# controller_left_bottom.net
KiCad netlist of a schematic drawn in EAGLE
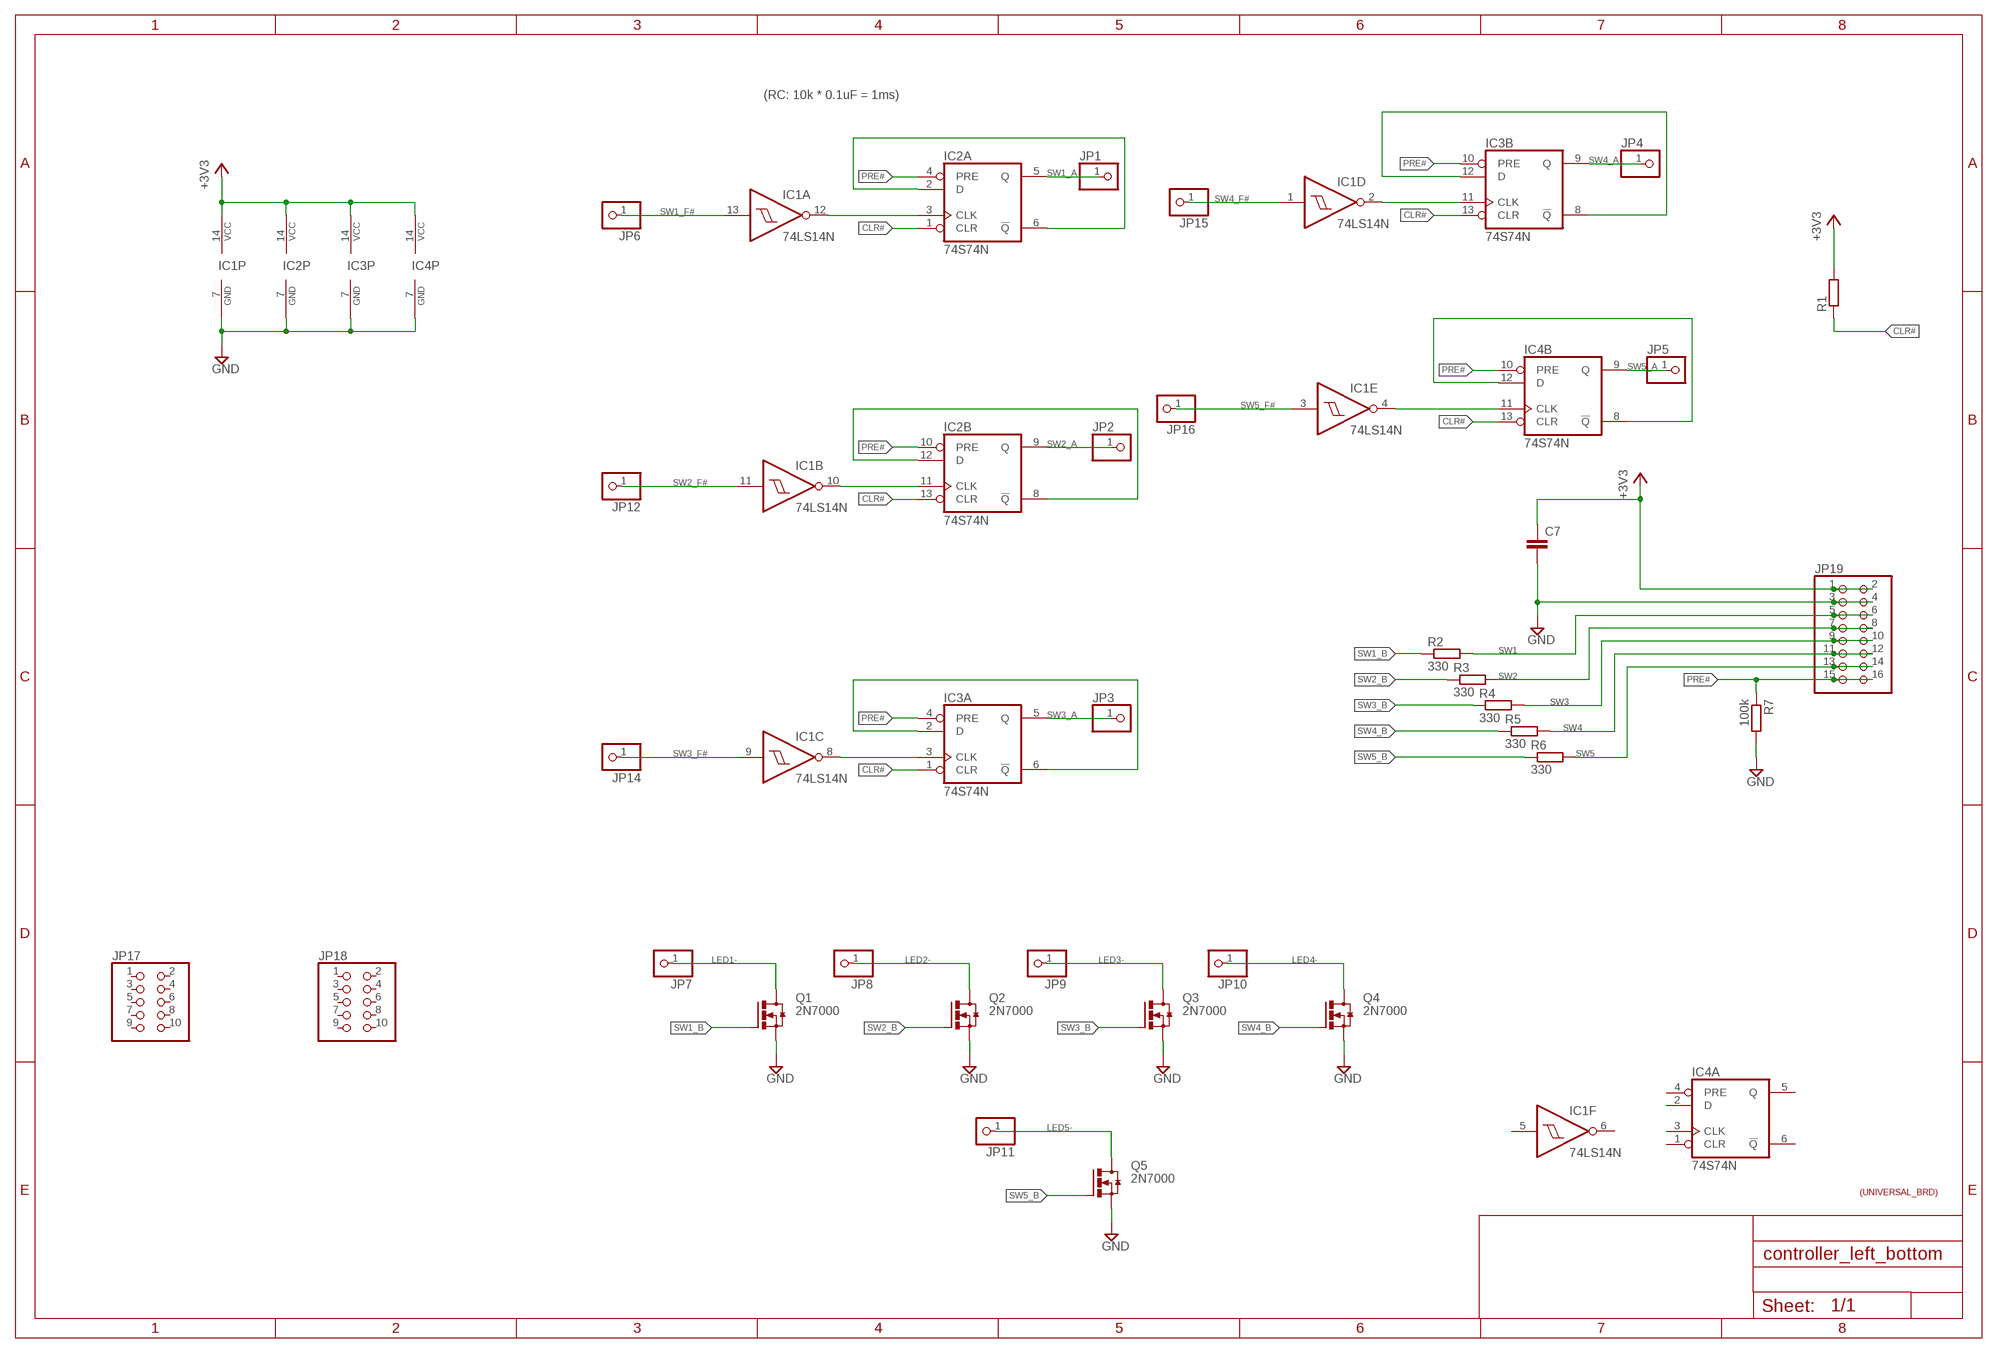
[diagram p0: schematic, sheet 1]

(export (version "E")
  (design (tool "Eeschema 10.0.6"))
  (components
    (comp (ref "C7")
      (value "C_DIP_2.54_1")
      (footprint "eagle-import:C_DIP2.54_1")
      (libsource (lib "eagle-import") (part "C_DIP_2.54_1"))
    )
    (comp (ref "IC1")
      (value "74LS14N")
      (footprint "eagle-import:DIL14")
      (libsource (lib "eagle-import") (part "7414NLS"))
    )
    (comp (ref "IC2")
      (value "74S74N")
      (footprint "eagle-import:DIL14")
      (libsource (lib "eagle-import") (part "7474NS"))
    )
    (comp (ref "IC3")
      (value "74S74N")
      (footprint "eagle-import:DIL14")
      (libsource (lib "eagle-import") (part "7474NS"))
    )
    (comp (ref "IC4")
      (value "74S74N")
      (footprint "eagle-import:DIL14")
      (libsource (lib "eagle-import") (part "7474NS"))
    )
    (comp (ref "JP1")
      (value "PINHD-1X1")
      (footprint "eagle-import:1X01_UNIVERSAL_BRD")
      (libsource (lib "eagle-import") (part "PINHD-1X1"))
    )
    (comp (ref "JP2")
      (value "PINHD-1X1")
      (footprint "eagle-import:1X01_UNIVERSAL_BRD")
      (libsource (lib "eagle-import") (part "PINHD-1X1"))
    )
    (comp (ref "JP3")
      (value "PINHD-1X1")
      (footprint "eagle-import:1X01_UNIVERSAL_BRD")
      (libsource (lib "eagle-import") (part "PINHD-1X1"))
    )
    (comp (ref "JP4")
      (value "PINHD-1X1")
      (footprint "eagle-import:1X01_UNIVERSAL_BRD")
      (libsource (lib "eagle-import") (part "PINHD-1X1"))
    )
    (comp (ref "JP5")
      (value "PINHD-1X1")
      (footprint "eagle-import:1X01_UNIVERSAL_BRD")
      (libsource (lib "eagle-import") (part "PINHD-1X1"))
    )
    (comp (ref "JP6")
      (value "PINHD-1X1")
      (footprint "eagle-import:1X01_UNIVERSAL_BRD")
      (libsource (lib "eagle-import") (part "PINHD-1X1"))
    )
    (comp (ref "JP7")
      (value "PINHD-1X1")
      (footprint "eagle-import:1X01_UNIVERSAL_BRD")
      (libsource (lib "eagle-import") (part "PINHD-1X1"))
    )
    (comp (ref "JP8")
      (value "PINHD-1X1")
      (footprint "eagle-import:1X01_UNIVERSAL_BRD")
      (libsource (lib "eagle-import") (part "PINHD-1X1"))
    )
    (comp (ref "JP9")
      (value "PINHD-1X1")
      (footprint "eagle-import:1X01_UNIVERSAL_BRD")
      (libsource (lib "eagle-import") (part "PINHD-1X1"))
    )
    (comp (ref "JP10")
      (value "PINHD-1X1")
      (footprint "eagle-import:1X01_UNIVERSAL_BRD")
      (libsource (lib "eagle-import") (part "PINHD-1X1"))
    )
    (comp (ref "JP11")
      (value "PINHD-1X1")
      (footprint "eagle-import:1X01_UNIVERSAL_BRD")
      (libsource (lib "eagle-import") (part "PINHD-1X1"))
    )
    (comp (ref "JP12")
      (value "PINHD-1X1")
      (footprint "eagle-import:1X01_UNIVERSAL_BRD")
      (libsource (lib "eagle-import") (part "PINHD-1X1"))
    )
    (comp (ref "JP14")
      (value "PINHD-1X1")
      (footprint "eagle-import:1X01_UNIVERSAL_BRD")
      (libsource (lib "eagle-import") (part "PINHD-1X1"))
    )
    (comp (ref "JP15")
      (value "PINHD-1X1")
      (footprint "eagle-import:1X01_UNIVERSAL_BRD")
      (libsource (lib "eagle-import") (part "PINHD-1X1"))
    )
    (comp (ref "JP16")
      (value "PINHD-1X1")
      (footprint "eagle-import:1X01_UNIVERSAL_BRD")
      (libsource (lib "eagle-import") (part "PINHD-1X1"))
    )
    (comp (ref "JP17")
      (value "PINHD-2X5")
      (footprint "eagle-import:2X05")
      (libsource (lib "eagle-import") (part "PINHD-2X5"))
    )
    (comp (ref "JP18")
      (value "PINHD-2X5")
      (footprint "eagle-import:2X05")
      (libsource (lib "eagle-import") (part "PINHD-2X5"))
    )
    (comp (ref "JP19")
      (value "PINHD-2X8")
      (footprint "eagle-import:2X08")
      (libsource (lib "eagle-import") (part "PINHD-2X8"))
    )
    (comp (ref "Q1")
      (value "2N7000")
      (footprint "eagle-import:TO92")
      (libsource (lib "eagle-import") (part "2N7000"))
    )
    (comp (ref "Q2")
      (value "2N7000")
      (footprint "eagle-import:TO92")
      (libsource (lib "eagle-import") (part "2N7000"))
    )
    (comp (ref "Q3")
      (value "2N7000")
      (footprint "eagle-import:TO92")
      (libsource (lib "eagle-import") (part "2N7000"))
    )
    (comp (ref "Q4")
      (value "2N7000")
      (footprint "eagle-import:TO92")
      (libsource (lib "eagle-import") (part "2N7000"))
    )
    (comp (ref "Q5")
      (value "2N7000")
      (footprint "eagle-import:TO92")
      (libsource (lib "eagle-import") (part "2N7000"))
    )
    (comp (ref "R1")
      (value "R_DIP_4")
      (footprint "eagle-import:R_DIP2.54_4")
      (libsource (lib "eagle-import") (part "R_DIP_4"))
    )
    (comp (ref "R2")
      (value "330")
      (footprint "eagle-import:R_DIP2.54_4")
      (libsource (lib "eagle-import") (part "R_DIP_4"))
    )
    (comp (ref "R3")
      (value "330")
      (footprint "eagle-import:R_DIP2.54_4")
      (libsource (lib "eagle-import") (part "R_DIP_4"))
    )
    (comp (ref "R4")
      (value "330")
      (footprint "eagle-import:R_DIP2.54_4")
      (libsource (lib "eagle-import") (part "R_DIP_4"))
    )
    (comp (ref "R5")
      (value "330")
      (footprint "eagle-import:R_DIP2.54_4")
      (libsource (lib "eagle-import") (part "R_DIP_4"))
    )
    (comp (ref "R6")
      (value "330")
      (footprint "eagle-import:R_DIP2.54_4")
      (libsource (lib "eagle-import") (part "R_DIP_4"))
    )
    (comp (ref "R7")
      (value "100k")
      (footprint "eagle-import:R_DIP2.54_4")
      (libsource (lib "eagle-import") (part "R_DIP_4"))
    )
    (comp (ref "U$1")
      (value "UNIVERSAL_BRD_95MM_72MM")
      (footprint "eagle-import:UNIVERSAL_BRD_95MM_72MM")
      (libsource (lib "eagle-import") (part "UNIVERSAL_BRD_95MM_72MM"))
    )
  )
  (nets
    (net (code "1") (name "+3V3") (class "Default")
      (node (ref "C7") (pin "1") (pinfunction "1_1") (pintype "passive"))
      (node (ref "IC1") (pin "14") (pinfunction "VCC_14") (pintype "power_in"))
      (node (ref "IC2") (pin "14") (pinfunction "VCC_14") (pintype "power_in"))
      (node (ref "IC3") (pin "14") (pinfunction "VCC_14") (pintype "power_in"))
      (node (ref "IC4") (pin "14") (pinfunction "VCC_14") (pintype "power_in"))
      (node (ref "JP19") (pin "1") (pinfunction "1_1") (pintype "passive"))
      (node (ref "JP19") (pin "2") (pinfunction "2_2") (pintype "passive"))
      (node (ref "R1") (pin "2") (pinfunction "2_2") (pintype "passive"))
    )
    (net (code "2") (name "/LED1-") (class "Default")
      (node (ref "JP7") (pin "1") (pinfunction "1_1") (pintype "passive"))
      (node (ref "Q1") (pin "D") (pinfunction "D_D") (pintype "passive"))
    )
    (net (code "3") (name "/LED2-") (class "Default")
      (node (ref "JP8") (pin "1") (pinfunction "1_1") (pintype "passive"))
      (node (ref "Q2") (pin "D") (pinfunction "D_D") (pintype "passive"))
    )
    (net (code "4") (name "/LED3-") (class "Default")
      (node (ref "JP9") (pin "1") (pinfunction "1_1") (pintype "passive"))
      (node (ref "Q3") (pin "D") (pinfunction "D_D") (pintype "passive"))
    )
    (net (code "5") (name "/LED4-") (class "Default")
      (node (ref "JP10") (pin "1") (pinfunction "1_1") (pintype "passive"))
      (node (ref "Q4") (pin "D") (pinfunction "D_D") (pintype "passive"))
    )
    (net (code "6") (name "/LED5-") (class "Default")
      (node (ref "JP11") (pin "1") (pinfunction "1_1") (pintype "passive"))
      (node (ref "Q5") (pin "D") (pinfunction "D_D") (pintype "passive"))
    )
    (net (code "7") (name "/SW1") (class "Default")
      (node (ref "JP19") (pin "5") (pinfunction "5_5") (pintype "passive"))
      (node (ref "JP19") (pin "6") (pinfunction "6_6") (pintype "passive"))
      (node (ref "R2") (pin "2") (pinfunction "2_2") (pintype "passive"))
    )
    (net (code "8") (name "/SW1_A") (class "Default")
      (node (ref "IC2") (pin "5") (pinfunction "Q_5") (pintype "output"))
      (node (ref "JP1") (pin "1") (pinfunction "1_1") (pintype "passive"))
    )
    (net (code "9") (name "/SW1_F#") (class "Default")
      (node (ref "IC1") (pin "13") (pinfunction "I_13") (pintype "input"))
      (node (ref "JP6") (pin "1") (pinfunction "1_1") (pintype "passive"))
    )
    (net (code "10") (name "/SW2") (class "Default")
      (node (ref "JP19") (pin "7") (pinfunction "7_7") (pintype "passive"))
      (node (ref "JP19") (pin "8") (pinfunction "8_8") (pintype "passive"))
      (node (ref "R3") (pin "2") (pinfunction "2_2") (pintype "passive"))
    )
    (net (code "11") (name "/SW2_A") (class "Default")
      (node (ref "IC2") (pin "9") (pinfunction "Q_9") (pintype "output"))
      (node (ref "JP2") (pin "1") (pinfunction "1_1") (pintype "passive"))
    )
    (net (code "12") (name "/SW2_F#") (class "Default")
      (node (ref "IC1") (pin "11") (pinfunction "I_11") (pintype "input"))
      (node (ref "JP12") (pin "1") (pinfunction "1_1") (pintype "passive"))
    )
    (net (code "13") (name "/SW3") (class "Default")
      (node (ref "JP19") (pin "10") (pinfunction "10_10") (pintype "passive"))
      (node (ref "JP19") (pin "9") (pinfunction "9_9") (pintype "passive"))
      (node (ref "R4") (pin "2") (pinfunction "2_2") (pintype "passive"))
    )
    (net (code "14") (name "/SW3_A") (class "Default")
      (node (ref "IC3") (pin "5") (pinfunction "Q_5") (pintype "output"))
      (node (ref "JP3") (pin "1") (pinfunction "1_1") (pintype "passive"))
    )
    (net (code "15") (name "/SW3_F#") (class "Default")
      (node (ref "IC1") (pin "9") (pinfunction "I_9") (pintype "input"))
      (node (ref "JP14") (pin "1") (pinfunction "1_1") (pintype "passive"))
    )
    (net (code "16") (name "/SW4") (class "Default")
      (node (ref "JP19") (pin "11") (pinfunction "11_11") (pintype "passive"))
      (node (ref "JP19") (pin "12") (pinfunction "12_12") (pintype "passive"))
      (node (ref "R5") (pin "2") (pinfunction "2_2") (pintype "passive"))
    )
    (net (code "17") (name "/SW4_A") (class "Default")
      (node (ref "IC3") (pin "9") (pinfunction "Q_9") (pintype "output"))
      (node (ref "JP4") (pin "1") (pinfunction "1_1") (pintype "passive"))
    )
    (net (code "18") (name "/SW4_F#") (class "Default")
      (node (ref "IC1") (pin "1") (pinfunction "I_1") (pintype "input"))
      (node (ref "JP15") (pin "1") (pinfunction "1_1") (pintype "passive"))
    )
    (net (code "19") (name "/SW5") (class "Default")
      (node (ref "JP19") (pin "13") (pinfunction "13_13") (pintype "passive"))
      (node (ref "JP19") (pin "14") (pinfunction "14_14") (pintype "passive"))
      (node (ref "R6") (pin "2") (pinfunction "2_2") (pintype "passive"))
    )
    (net (code "20") (name "/SW5_A") (class "Default")
      (node (ref "IC4") (pin "9") (pinfunction "Q_9") (pintype "output"))
      (node (ref "JP5") (pin "1") (pinfunction "1_1") (pintype "passive"))
    )
    (net (code "21") (name "/SW5_F#") (class "Default")
      (node (ref "IC1") (pin "3") (pinfunction "I_3") (pintype "input"))
      (node (ref "JP16") (pin "1") (pinfunction "1_1") (pintype "passive"))
    )
    (net (code "22") (name "CLR#") (class "Default")
      (node (ref "IC2") (pin "1") (pinfunction "CLR_1") (pintype "input"))
      (node (ref "IC2") (pin "13") (pinfunction "CLR_13") (pintype "input"))
      (node (ref "IC3") (pin "1") (pinfunction "CLR_1") (pintype "input"))
      (node (ref "IC3") (pin "13") (pinfunction "CLR_13") (pintype "input"))
      (node (ref "IC4") (pin "13") (pinfunction "CLR_13") (pintype "input"))
      (node (ref "R1") (pin "1") (pinfunction "1_1") (pintype "passive"))
    )
    (net (code "23") (name "GND") (class "Default")
      (node (ref "C7") (pin "2") (pinfunction "2_2") (pintype "passive"))
      (node (ref "IC1") (pin "7") (pinfunction "GND_7") (pintype "power_in"))
      (node (ref "IC2") (pin "7") (pinfunction "GND_7") (pintype "power_in"))
      (node (ref "IC3") (pin "7") (pinfunction "GND_7") (pintype "power_in"))
      (node (ref "IC4") (pin "7") (pinfunction "GND_7") (pintype "power_in"))
      (node (ref "JP19") (pin "3") (pinfunction "3_3") (pintype "passive"))
      (node (ref "JP19") (pin "4") (pinfunction "4_4") (pintype "passive"))
      (node (ref "Q1") (pin "S") (pinfunction "S_S") (pintype "passive"))
      (node (ref "Q2") (pin "S") (pinfunction "S_S") (pintype "passive"))
      (node (ref "Q3") (pin "S") (pinfunction "S_S") (pintype "passive"))
      (node (ref "Q4") (pin "S") (pinfunction "S_S") (pintype "passive"))
      (node (ref "Q5") (pin "S") (pinfunction "S_S") (pintype "passive"))
      (node (ref "R7") (pin "2") (pinfunction "2_2") (pintype "passive"))
    )
    (net (code "24") (name "Net-(IC1A-O)") (class "Default")
      (node (ref "IC1") (pin "12") (pinfunction "O_12") (pintype "output"))
      (node (ref "IC2") (pin "3") (pinfunction "CLK_3") (pintype "input"))
    )
    (net (code "25") (name "Net-(IC1B-O)") (class "Default")
      (node (ref "IC1") (pin "10") (pinfunction "O_10") (pintype "output"))
      (node (ref "IC2") (pin "11") (pinfunction "CLK_11") (pintype "input"))
    )
    (net (code "26") (name "Net-(IC1C-O)") (class "Default")
      (node (ref "IC1") (pin "8") (pinfunction "O_8") (pintype "output"))
      (node (ref "IC3") (pin "3") (pinfunction "CLK_3") (pintype "input"))
    )
    (net (code "27") (name "Net-(IC1D-O)") (class "Default")
      (node (ref "IC1") (pin "2") (pinfunction "O_2") (pintype "output"))
      (node (ref "IC3") (pin "11") (pinfunction "CLK_11") (pintype "input"))
    )
    (net (code "28") (name "Net-(IC1E-O)") (class "Default")
      (node (ref "IC1") (pin "4") (pinfunction "O_4") (pintype "output"))
      (node (ref "IC4") (pin "11") (pinfunction "CLK_11") (pintype "input"))
    )
    (net (code "29") (name "Net-(IC2A-D)") (class "Default")
      (node (ref "IC2") (pin "2") (pinfunction "D_2") (pintype "input"))
      (node (ref "IC2") (pin "6") (pinfunction "~{Q}_6") (pintype "output"))
    )
    (net (code "30") (name "Net-(IC2B-D)") (class "Default")
      (node (ref "IC2") (pin "12") (pinfunction "D_12") (pintype "input"))
      (node (ref "IC2") (pin "8") (pinfunction "~{Q}_8") (pintype "output"))
    )
    (net (code "31") (name "Net-(IC3A-D)") (class "Default")
      (node (ref "IC3") (pin "2") (pinfunction "D_2") (pintype "input"))
      (node (ref "IC3") (pin "6") (pinfunction "~{Q}_6") (pintype "output"))
    )
    (net (code "32") (name "Net-(IC3B-D)") (class "Default")
      (node (ref "IC3") (pin "12") (pinfunction "D_12") (pintype "input"))
      (node (ref "IC3") (pin "8") (pinfunction "~{Q}_8") (pintype "output"))
    )
    (net (code "33") (name "Net-(IC4B-D)") (class "Default")
      (node (ref "IC4") (pin "12") (pinfunction "D_12") (pintype "input"))
      (node (ref "IC4") (pin "8") (pinfunction "~{Q}_8") (pintype "output"))
    )
    (net (code "34") (name "PRE#") (class "Default")
      (node (ref "IC2") (pin "10") (pinfunction "PRE_10") (pintype "input"))
      (node (ref "IC2") (pin "4") (pinfunction "PRE_4") (pintype "input"))
      (node (ref "IC3") (pin "10") (pinfunction "PRE_10") (pintype "input"))
      (node (ref "IC3") (pin "4") (pinfunction "PRE_4") (pintype "input"))
      (node (ref "IC4") (pin "10") (pinfunction "PRE_10") (pintype "input"))
      (node (ref "JP19") (pin "15") (pinfunction "15_15") (pintype "passive"))
      (node (ref "JP19") (pin "16") (pinfunction "16_16") (pintype "passive"))
      (node (ref "R7") (pin "1") (pinfunction "1_1") (pintype "passive"))
    )
    (net (code "35") (name "SW1_B") (class "Default")
      (node (ref "Q1") (pin "G") (pinfunction "G_G") (pintype "passive"))
      (node (ref "R2") (pin "1") (pinfunction "1_1") (pintype "passive"))
    )
    (net (code "36") (name "SW2_B") (class "Default")
      (node (ref "Q2") (pin "G") (pinfunction "G_G") (pintype "passive"))
      (node (ref "R3") (pin "1") (pinfunction "1_1") (pintype "passive"))
    )
    (net (code "37") (name "SW3_B") (class "Default")
      (node (ref "Q3") (pin "G") (pinfunction "G_G") (pintype "passive"))
      (node (ref "R4") (pin "1") (pinfunction "1_1") (pintype "passive"))
    )
    (net (code "38") (name "SW4_B") (class "Default")
      (node (ref "Q4") (pin "G") (pinfunction "G_G") (pintype "passive"))
      (node (ref "R5") (pin "1") (pinfunction "1_1") (pintype "passive"))
    )
    (net (code "39") (name "SW5_B") (class "Default")
      (node (ref "Q5") (pin "G") (pinfunction "G_G") (pintype "passive"))
      (node (ref "R6") (pin "1") (pinfunction "1_1") (pintype "passive"))
    )
    (net (code "40") (name "unconnected-(IC1F-I-Pad5)") (class "Default")
      (node (ref "IC1") (pin "5") (pinfunction "I_5") (pintype "input"))
    )
    (net (code "41") (name "unconnected-(IC1F-O-Pad6)") (class "Default")
      (node (ref "IC1") (pin "6") (pinfunction "O_6") (pintype "output"))
    )
    (net (code "42") (name "unconnected-(IC4A-CLK-Pad3)") (class "Default")
      (node (ref "IC4") (pin "3") (pinfunction "CLK_3") (pintype "input"))
    )
    (net (code "43") (name "unconnected-(IC4A-CLR-Pad1)") (class "Default")
      (node (ref "IC4") (pin "1") (pinfunction "CLR_1") (pintype "input"))
    )
    (net (code "44") (name "unconnected-(IC4A-D-Pad2)") (class "Default")
      (node (ref "IC4") (pin "2") (pinfunction "D_2") (pintype "input"))
    )
    (net (code "45") (name "unconnected-(IC4A-PRE-Pad4)") (class "Default")
      (node (ref "IC4") (pin "4") (pinfunction "PRE_4") (pintype "input"))
    )
    (net (code "46") (name "unconnected-(IC4A-Q-Pad5)") (class "Default")
      (node (ref "IC4") (pin "5") (pinfunction "Q_5") (pintype "output"))
    )
    (net (code "47") (name "unconnected-(IC4A-~{Q}-Pad6)") (class "Default")
      (node (ref "IC4") (pin "6") (pinfunction "~{Q}_6") (pintype "output"))
    )
    (net (code "48") (name "unconnected-(JP17-Pad1)") (class "Default")
      (node (ref "JP17") (pin "1") (pinfunction "1_1") (pintype "passive"))
    )
    (net (code "49") (name "unconnected-(JP17-Pad2)") (class "Default")
      (node (ref "JP17") (pin "2") (pinfunction "2_2") (pintype "passive"))
    )
    (net (code "50") (name "unconnected-(JP17-Pad3)") (class "Default")
      (node (ref "JP17") (pin "3") (pinfunction "3_3") (pintype "passive"))
    )
    (net (code "51") (name "unconnected-(JP17-Pad4)") (class "Default")
      (node (ref "JP17") (pin "4") (pinfunction "4_4") (pintype "passive"))
    )
    (net (code "52") (name "unconnected-(JP17-Pad5)") (class "Default")
      (node (ref "JP17") (pin "5") (pinfunction "5_5") (pintype "passive"))
    )
    (net (code "53") (name "unconnected-(JP17-Pad6)") (class "Default")
      (node (ref "JP17") (pin "6") (pinfunction "6_6") (pintype "passive"))
    )
    (net (code "54") (name "unconnected-(JP17-Pad7)") (class "Default")
      (node (ref "JP17") (pin "7") (pinfunction "7_7") (pintype "passive"))
    )
    (net (code "55") (name "unconnected-(JP17-Pad8)") (class "Default")
      (node (ref "JP17") (pin "8") (pinfunction "8_8") (pintype "passive"))
    )
    (net (code "56") (name "unconnected-(JP17-Pad9)") (class "Default")
      (node (ref "JP17") (pin "9") (pinfunction "9_9") (pintype "passive"))
    )
    (net (code "57") (name "unconnected-(JP17-Pad10)") (class "Default")
      (node (ref "JP17") (pin "10") (pinfunction "10_10") (pintype "passive"))
    )
    (net (code "58") (name "unconnected-(JP18-Pad1)") (class "Default")
      (node (ref "JP18") (pin "1") (pinfunction "1_1") (pintype "passive"))
    )
    (net (code "59") (name "unconnected-(JP18-Pad2)") (class "Default")
      (node (ref "JP18") (pin "2") (pinfunction "2_2") (pintype "passive"))
    )
    (net (code "60") (name "unconnected-(JP18-Pad3)") (class "Default")
      (node (ref "JP18") (pin "3") (pinfunction "3_3") (pintype "passive"))
    )
    (net (code "61") (name "unconnected-(JP18-Pad4)") (class "Default")
      (node (ref "JP18") (pin "4") (pinfunction "4_4") (pintype "passive"))
    )
    (net (code "62") (name "unconnected-(JP18-Pad5)") (class "Default")
      (node (ref "JP18") (pin "5") (pinfunction "5_5") (pintype "passive"))
    )
    (net (code "63") (name "unconnected-(JP18-Pad6)") (class "Default")
      (node (ref "JP18") (pin "6") (pinfunction "6_6") (pintype "passive"))
    )
    (net (code "64") (name "unconnected-(JP18-Pad7)") (class "Default")
      (node (ref "JP18") (pin "7") (pinfunction "7_7") (pintype "passive"))
    )
    (net (code "65") (name "unconnected-(JP18-Pad8)") (class "Default")
      (node (ref "JP18") (pin "8") (pinfunction "8_8") (pintype "passive"))
    )
    (net (code "66") (name "unconnected-(JP18-Pad9)") (class "Default")
      (node (ref "JP18") (pin "9") (pinfunction "9_9") (pintype "passive"))
    )
    (net (code "67") (name "unconnected-(JP18-Pad10)") (class "Default")
      (node (ref "JP18") (pin "10") (pinfunction "10_10") (pintype "passive"))
    )
  )
)
